# CAN-Interface.net
KiCad netlist of a schematic drawn in EAGLE
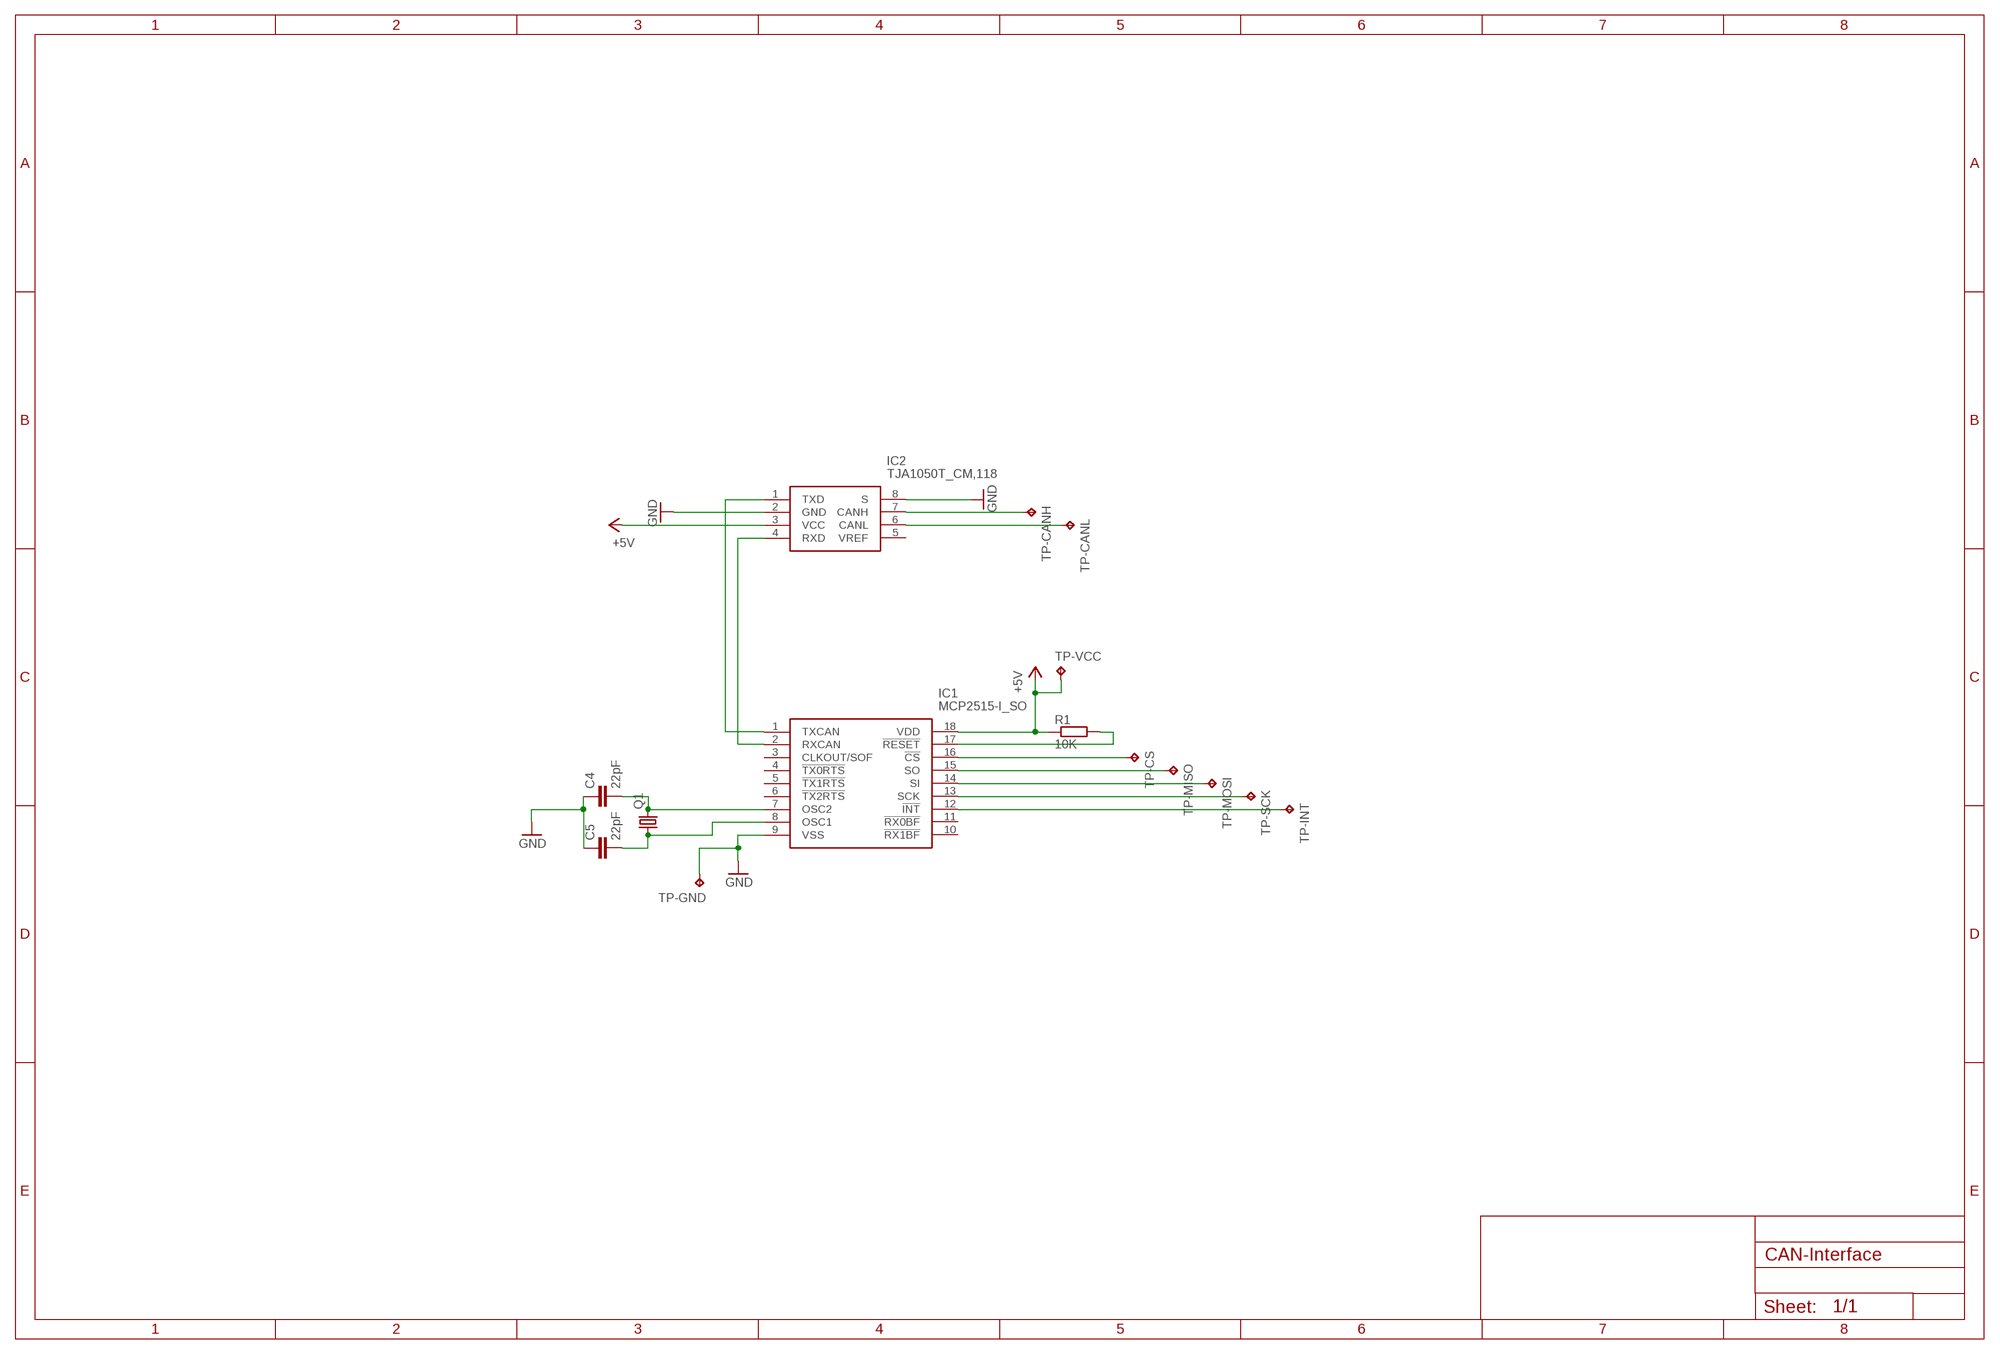
[diagram p0: schematic, sheet 1]

(export (version "E")
  (design (tool "Eeschema 10.0.6"))
  (components
    (comp (ref "C4")
      (value "22pF")
      (footprint "eagle-import:C025-050X050")
      (libsource (lib "eagle-import") (part "C-EU025-050X050"))
    )
    (comp (ref "C5")
      (value "22pF")
      (footprint "eagle-import:C025-050X050")
      (libsource (lib "eagle-import") (part "C-EU025-050X050"))
    )
    (comp (ref "IC1")
      (value "MCP2515-I_SO")
      (footprint "eagle-import:SOIC127P1030X265-18N")
      (fields
        (field (name "MANUFACTURER_PART_NUMBER") "MCP2515-I/SO")
        (field (name "MOUSER_PART_NUMBER") "579-MCP2515-I/SO")
      )
      (libsource (lib "eagle-import") (part "MCP2515-I_SO"))
    )
    (comp (ref "IC2")
      (value "TJA1050T_CM,118")
      (footprint "eagle-import:SOIC127P600X175-8N")
      (fields
        (field (name "MANUFACTURER_PART_NUMBER") "TJA1050T/CM,118")
        (field (name "MOUSER_PART_NUMBER") "771-TJA1050T/CM118")
      )
      (libsource (lib "eagle-import") (part "TJA1050T_CM,118"))
    )
    (comp (ref "Q1")
      (value "CRYSTALHC49S")
      (footprint "eagle-import:HC49_S")
      (libsource (lib "eagle-import") (part "CRYSTALHC49S"))
    )
    (comp (ref "R1")
      (value "10K")
      (footprint "eagle-import:0204_7")
      (libsource (lib "eagle-import") (part "R-EU_0204/7"))
    )
    (comp (ref "TP-CANH")
      (value "TPB1,27")
      (footprint "eagle-import:B1,27")
      (libsource (lib "eagle-import") (part "TPB1,27"))
    )
    (comp (ref "TP-CANL")
      (value "TPB1,27")
      (footprint "eagle-import:B1,27")
      (libsource (lib "eagle-import") (part "TPB1,27"))
    )
    (comp (ref "TP-CS")
      (value "TPB1,27")
      (footprint "eagle-import:B1,27")
      (libsource (lib "eagle-import") (part "TPB1,27"))
    )
    (comp (ref "TP-GND")
      (value "TPB1,27")
      (footprint "eagle-import:B1,27")
      (libsource (lib "eagle-import") (part "TPB1,27"))
    )
    (comp (ref "TP-INT")
      (value "TPB1,27")
      (footprint "eagle-import:B1,27")
      (libsource (lib "eagle-import") (part "TPB1,27"))
    )
    (comp (ref "TP-MISO")
      (value "TPB1,27")
      (footprint "eagle-import:B1,27")
      (libsource (lib "eagle-import") (part "TPB1,27"))
    )
    (comp (ref "TP-MOSI")
      (value "TPB1,27")
      (footprint "eagle-import:B1,27")
      (libsource (lib "eagle-import") (part "TPB1,27"))
    )
    (comp (ref "TP-SCK")
      (value "TPB1,27")
      (footprint "eagle-import:B1,27")
      (libsource (lib "eagle-import") (part "TPB1,27"))
    )
    (comp (ref "TP-VCC")
      (value "TPB1,27")
      (footprint "eagle-import:B1,27")
      (libsource (lib "eagle-import") (part "TPB1,27"))
    )
  )
  (nets
    (net (code "1") (name "+5V") (class "Default")
      (node (ref "IC1") (pin "18") (pinfunction "VDD_18") (pintype "power_in"))
      (node (ref "IC2") (pin "3") (pinfunction "VCC_3") (pintype "bidirectional"))
      (node (ref "R1") (pin "1") (pinfunction "1_1") (pintype "passive"))
      (node (ref "TP-VCC") (pin "TP") (pinfunction "TP_TP") (pintype "input"))
    )
    (net (code "2") (name "GND") (class "Default")
      (node (ref "C4") (pin "1") (pinfunction "1_1") (pintype "passive"))
      (node (ref "C5") (pin "1") (pinfunction "1_1") (pintype "passive"))
      (node (ref "IC1") (pin "9") (pinfunction "VSS_9") (pintype "power_in"))
      (node (ref "IC2") (pin "2") (pinfunction "GND_2") (pintype "bidirectional"))
      (node (ref "IC2") (pin "8") (pinfunction "S_8") (pintype "bidirectional"))
      (node (ref "TP-GND") (pin "TP") (pinfunction "TP_TP") (pintype "input"))
    )
    (net (code "3") (name "Net-(IC1-OSC1)") (class "Default")
      (node (ref "C5") (pin "2") (pinfunction "2_2") (pintype "passive"))
      (node (ref "IC1") (pin "8") (pinfunction "OSC1_8") (pintype "bidirectional"))
      (node (ref "Q1") (pin "1") (pinfunction "1_1") (pintype "passive"))
    )
    (net (code "4") (name "Net-(IC1-OSC2)") (class "Default")
      (node (ref "C4") (pin "2") (pinfunction "2_2") (pintype "passive"))
      (node (ref "IC1") (pin "7") (pinfunction "OSC2_7") (pintype "bidirectional"))
      (node (ref "Q1") (pin "2") (pinfunction "2_2") (pintype "passive"))
    )
    (net (code "5") (name "Net-(IC1-RXCAN)") (class "Default")
      (node (ref "IC1") (pin "2") (pinfunction "RXCAN_2") (pintype "bidirectional"))
      (node (ref "IC2") (pin "4") (pinfunction "RXD_4") (pintype "bidirectional"))
    )
    (net (code "6") (name "Net-(IC1-SCK)") (class "Default")
      (node (ref "IC1") (pin "13") (pinfunction "SCK_13") (pintype "bidirectional"))
      (node (ref "TP-SCK") (pin "TP") (pinfunction "TP_TP") (pintype "input"))
    )
    (net (code "7") (name "Net-(IC1-SI)") (class "Default")
      (node (ref "IC1") (pin "14") (pinfunction "SI_14") (pintype "bidirectional"))
      (node (ref "TP-MOSI") (pin "TP") (pinfunction "TP_TP") (pintype "input"))
    )
    (net (code "8") (name "Net-(IC1-SO)") (class "Default")
      (node (ref "IC1") (pin "15") (pinfunction "SO_15") (pintype "bidirectional"))
      (node (ref "TP-MISO") (pin "TP") (pinfunction "TP_TP") (pintype "input"))
    )
    (net (code "9") (name "Net-(IC1-TXCAN)") (class "Default")
      (node (ref "IC1") (pin "1") (pinfunction "TXCAN_1") (pintype "bidirectional"))
      (node (ref "IC2") (pin "1") (pinfunction "TXD_1") (pintype "bidirectional"))
    )
    (net (code "10") (name "Net-(IC1-~{CS})") (class "Default")
      (node (ref "IC1") (pin "16") (pinfunction "~{CS}_16") (pintype "input"))
      (node (ref "TP-CS") (pin "TP") (pinfunction "TP_TP") (pintype "input"))
    )
    (net (code "11") (name "Net-(IC1-~{INT})") (class "Default")
      (node (ref "IC1") (pin "12") (pinfunction "~{INT}_12") (pintype "input"))
      (node (ref "TP-INT") (pin "TP") (pinfunction "TP_TP") (pintype "input"))
    )
    (net (code "12") (name "Net-(IC1-~{RESET})") (class "Default")
      (node (ref "IC1") (pin "17") (pinfunction "~{RESET}_17") (pintype "bidirectional"))
      (node (ref "R1") (pin "2") (pinfunction "2_2") (pintype "passive"))
    )
    (net (code "13") (name "Net-(IC2-CANH)") (class "Default")
      (node (ref "IC2") (pin "7") (pinfunction "CANH_7") (pintype "bidirectional"))
      (node (ref "TP-CANH") (pin "TP") (pinfunction "TP_TP") (pintype "input"))
    )
    (net (code "14") (name "Net-(IC2-CANL)") (class "Default")
      (node (ref "IC2") (pin "6") (pinfunction "CANL_6") (pintype "bidirectional"))
      (node (ref "TP-CANL") (pin "TP") (pinfunction "TP_TP") (pintype "input"))
    )
    (net (code "15") (name "unconnected-(IC1-CLKOUT{slash}SOF-Pad3)") (class "Default")
      (node (ref "IC1") (pin "3") (pinfunction "CLKOUT/SOF_3") (pintype "output"))
    )
    (net (code "16") (name "unconnected-(IC1-~{RX0BF}-Pad11)") (class "Default")
      (node (ref "IC1") (pin "11") (pinfunction "~{RX0BF}_11") (pintype "bidirectional"))
    )
    (net (code "17") (name "unconnected-(IC1-~{RX1BF}-Pad10)") (class "Default")
      (node (ref "IC1") (pin "10") (pinfunction "~{RX1BF}_10") (pintype "bidirectional"))
    )
    (net (code "18") (name "unconnected-(IC1-~{TX0RTS}-Pad4)") (class "Default")
      (node (ref "IC1") (pin "4") (pinfunction "~{TX0RTS}_4") (pintype "bidirectional"))
    )
    (net (code "19") (name "unconnected-(IC1-~{TX1RTS}-Pad5)") (class "Default")
      (node (ref "IC1") (pin "5") (pinfunction "~{TX1RTS}_5") (pintype "bidirectional"))
    )
    (net (code "20") (name "unconnected-(IC1-~{TX2RTS}-Pad6)") (class "Default")
      (node (ref "IC1") (pin "6") (pinfunction "~{TX2RTS}_6") (pintype "bidirectional"))
    )
    (net (code "21") (name "unconnected-(IC2-VREF-Pad5)") (class "Default")
      (node (ref "IC2") (pin "5") (pinfunction "VREF_5") (pintype "bidirectional"))
    )
  )
)
